# Sheet1.net
KiCad netlist of a schematic drawn in Altium Designer
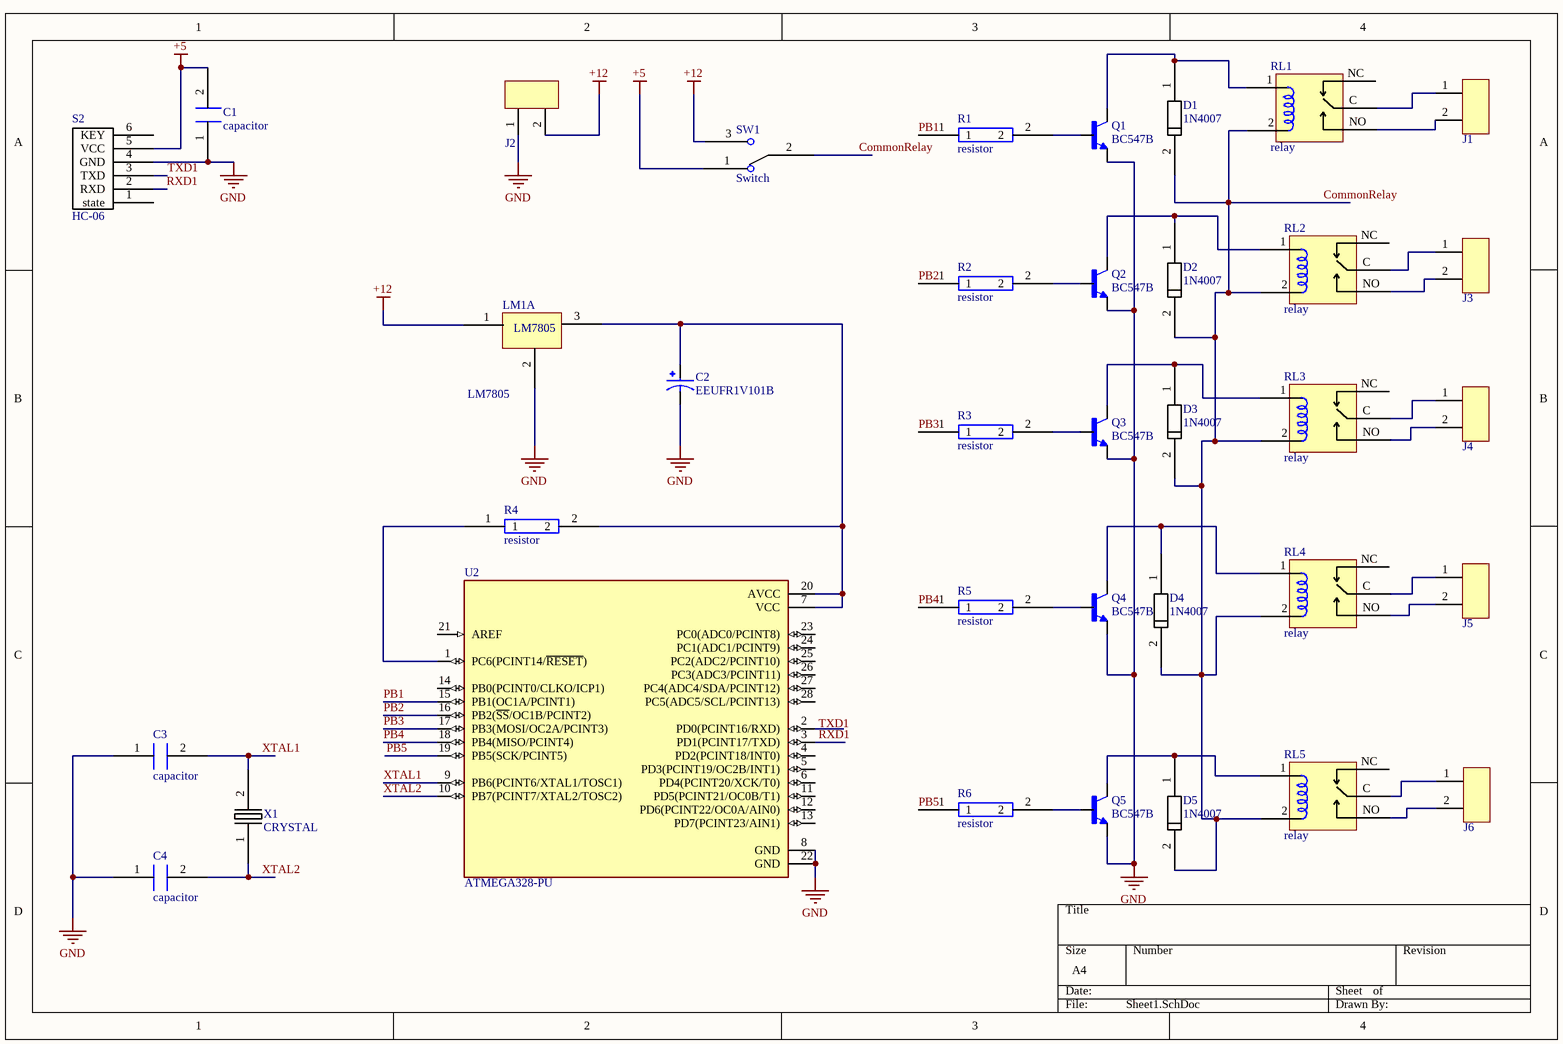
[diagram p0: Sheet1.SchDoc]

(export (version "E")
  (design (tool "Eeschema 10.0.6"))
  (components
    (comp (ref "C1")
      (value "capacitor")
      (footprint "Capacitor")
      (libsource (lib "Schlib1") (part "capacitor"))
    )
    (comp (ref "C2")
      (value "EEUFR1V101B")
      (footprint "CAPPRD350W60D800H1150")
      (description "AL LYTIC, RADIAL, 35VDC, 100UF")
      (fields (field (name "MF") "Panasonic"))
      (libsource (lib "EEUFR1V101B") (part "EEUFR1V101B"))
    )
    (comp (ref "C3")
      (value "capacitor")
      (footprint "Capacitor")
      (libsource (lib "Schlib1") (part "capacitor"))
    )
    (comp (ref "C4")
      (value "capacitor")
      (footprint "Capacitor")
      (libsource (lib "Schlib1") (part "capacitor"))
    )
    (comp (ref "D1") (value "1N4007") (footprint "1N4007") (libsource (lib "Schlib1") (part "1N4007")))
    (comp (ref "D2") (value "1N4007") (footprint "1N4007") (libsource (lib "Schlib1") (part "1N4007")))
    (comp (ref "D3") (value "1N4007") (footprint "1N4007") (libsource (lib "Schlib1") (part "1N4007")))
    (comp (ref "D4") (value "1N4007") (footprint "1N4007") (libsource (lib "Schlib1") (part "1N4007")))
    (comp (ref "D5") (value "1N4007") (footprint "1N4007") (libsource (lib "Schlib1") (part "1N4007")))
    (comp (ref "J1")
      (value "TBP01R1-508-02BE")
      (footprint "TBP01R1-508")
      (description "Conn Shrouded Header HDR 2 POS 5.08mm Solder RA Side Entry Thru-Hole Bag")
      (fields (field (name "MANUFACTURER") "CUI") (field (name "DESIGNED BY") "BERK"))
      (libsource (lib "UDEMY_Library") (part "TBP01R1-508-02BE"))
    )
    (comp (ref "J2")
      (value "TBP01R1-508-02BE")
      (footprint "TBP01R1-508")
      (description "Conn Shrouded Header HDR 2 POS 5.08mm Solder RA Side Entry Thru-Hole Bag")
      (fields (field (name "MANUFACTURER") "CUI") (field (name "DESIGNED BY") "BERK"))
      (libsource (lib "") (part "TBP01R1-508-02BE_1"))
    )
    (comp (ref "J3")
      (value "TBP01R1-508-02BE")
      (footprint "TBP01R1-508")
      (description "Conn Shrouded Header HDR 2 POS 5.08mm Solder RA Side Entry Thru-Hole Bag")
      (fields (field (name "MANUFACTURER") "CUI") (field (name "DESIGNED BY") "BERK"))
      (libsource (lib "UDEMY_Library") (part "TBP01R1-508-02BE"))
    )
    (comp (ref "J4")
      (value "TBP01R1-508-02BE")
      (footprint "TBP01R1-508")
      (description "Conn Shrouded Header HDR 2 POS 5.08mm Solder RA Side Entry Thru-Hole Bag")
      (fields (field (name "MANUFACTURER") "CUI") (field (name "DESIGNED BY") "BERK"))
      (libsource (lib "UDEMY_Library") (part "TBP01R1-508-02BE"))
    )
    (comp (ref "J5")
      (value "TBP01R1-508-02BE")
      (footprint "TBP01R1-508")
      (description "Conn Shrouded Header HDR 2 POS 5.08mm Solder RA Side Entry Thru-Hole Bag")
      (fields (field (name "MANUFACTURER") "CUI") (field (name "DESIGNED BY") "BERK"))
      (libsource (lib "UDEMY_Library") (part "TBP01R1-508-02BE"))
    )
    (comp (ref "J6")
      (value "TBP01R1-508-02BE")
      (footprint "TBP01R1-508")
      (description "Conn Shrouded Header HDR 2 POS 5.08mm Solder RA Side Entry Thru-Hole Bag")
      (fields (field (name "MANUFACTURER") "CUI") (field (name "DESIGNED BY") "BERK"))
      (libsource (lib "UDEMY_Library") (part "TBP01R1-508-02BE"))
    )
    (comp (ref "LM1") (value "LM7805") (footprint "LM7805") (libsource (lib "Schlib1") (part "LM7805")))
    (comp (ref "Q1")
      (value "BC547B")
      (footprint "TO92250P510H770-3")
      (description "Bipolar (BJT) Transistor NPN 45 V 100 mA 300MHz 625 mW Through Hole TO-92 (TO-226)")
      (fields (field (name "MF") "ON Semiconductor"))
      (libsource (lib "BC547B") (part "BC547B"))
    )
    (comp (ref "Q2")
      (value "BC547B")
      (footprint "TO92250P510H770-3")
      (description "Bipolar (BJT) Transistor NPN 45 V 100 mA 300MHz 625 mW Through Hole TO-92 (TO-226)")
      (fields (field (name "MF") "ON Semiconductor"))
      (libsource (lib "BC547B") (part "BC547B"))
    )
    (comp (ref "Q3")
      (value "BC547B")
      (footprint "TO92250P510H770-3")
      (description "Bipolar (BJT) Transistor NPN 45 V 100 mA 300MHz 625 mW Through Hole TO-92 (TO-226)")
      (fields (field (name "MF") "ON Semiconductor"))
      (libsource (lib "BC547B") (part "BC547B"))
    )
    (comp (ref "Q4")
      (value "BC547B")
      (footprint "TO92250P510H770-3")
      (description "Bipolar (BJT) Transistor NPN 45 V 100 mA 300MHz 625 mW Through Hole TO-92 (TO-226)")
      (fields (field (name "MF") "ON Semiconductor"))
      (libsource (lib "BC547B") (part "BC547B"))
    )
    (comp (ref "Q5")
      (value "BC547B")
      (footprint "TO92250P510H770-3")
      (description "Bipolar (BJT) Transistor NPN 45 V 100 mA 300MHz 625 mW Through Hole TO-92 (TO-226)")
      (fields (field (name "MF") "ON Semiconductor"))
      (libsource (lib "BC547B") (part "BC547B"))
    )
    (comp (ref "R1") (value "resistor") (footprint "res") (libsource (lib "Schlib1") (part "resistor")))
    (comp (ref "R2") (value "resistor") (footprint "res") (libsource (lib "Schlib1") (part "resistor")))
    (comp (ref "R3") (value "resistor") (footprint "res") (libsource (lib "Schlib1") (part "resistor")))
    (comp (ref "R4") (value "resistor") (footprint "res") (libsource (lib "Schlib1") (part "resistor")))
    (comp (ref "R5") (value "resistor") (footprint "res") (libsource (lib "Schlib1") (part "resistor")))
    (comp (ref "R6") (value "resistor") (footprint "res") (libsource (lib "Schlib1") (part "resistor")))
    (comp (ref "RL1") (value "relay") (footprint "relay") (libsource (lib "Schlib1") (part "relay")))
    (comp (ref "RL2") (value "relay") (footprint "relay") (libsource (lib "Schlib1") (part "relay")))
    (comp (ref "RL3") (value "relay") (footprint "relay") (libsource (lib "Schlib1") (part "relay")))
    (comp (ref "RL4") (value "relay") (footprint "relay") (libsource (lib "Schlib1") (part "relay")))
    (comp (ref "RL5") (value "relay") (footprint "relay") (libsource (lib "Schlib1") (part "relay")))
    (comp (ref "S2") (value "HC-06") (footprint "HC-06") (libsource (lib "Schlib1") (part "HC-06")))
    (comp (ref "SW1")
      (value "Switch")
      (footprint "toggle switch")
      (libsource (lib "Schlib1") (part "Switch"))
    )
    (comp (ref "U2")
      (value "ATMEGA328-PU")
      (footprint "DIP787W46P254L3467H508Q28")
      (description "AVR AVRÂ® ATmega Microcontroller IC 8-Bit 20MHz 32KB (16K x 16) FLASH 28-PDIP")
      (fields (field (name "MF") "Microchip Technology"))
      (libsource (lib "ATMEGA328-PU") (part "ATMEGA328-PU"))
    )
    (comp (ref "X1") (value "CRYSTAL") (footprint "CRYSTAL") (libsource (lib "Schlib1") (part "CRYSTAL")))
  )
  (nets
    (net (code "1") (name "+5") (class "Default")
      (node (ref "C1") (pin "2") (pintype "passive"))
      (node (ref "S2") (pin "5") (pinfunction "VCC_5") (pintype "passive"))
      (node (ref "SW1") (pin "1") (pinfunction "1_1") (pintype "passive"))
    )
    (net (code "2") (name "+12") (class "Default")
      (node (ref "J2") (pin "2") (pinfunction "2_2") (pintype "power_in"))
      (node (ref "LM1") (pin "1") (pinfunction "in_1") (pintype "passive"))
      (node (ref "SW1") (pin "3") (pinfunction "3_3") (pintype "passive"))
    )
    (net (code "3") (name "/CommonRelay") (class "Default")
      (node (ref "D1") (pin "2") (pinfunction "katot_2") (pintype "passive"))
      (node (ref "D2") (pin "2") (pinfunction "katot_2") (pintype "passive"))
      (node (ref "D3") (pin "2") (pinfunction "katot_2") (pintype "passive"))
      (node (ref "D4") (pin "2") (pinfunction "katot_2") (pintype "passive"))
      (node (ref "D5") (pin "2") (pinfunction "katot_2") (pintype "passive"))
      (node (ref "RL1") (pin "2") (pinfunction "2_2") (pintype "passive"))
      (node (ref "RL2") (pin "2") (pinfunction "2_2") (pintype "passive"))
      (node (ref "RL3") (pin "2") (pinfunction "2_2") (pintype "passive"))
      (node (ref "RL4") (pin "2") (pinfunction "2_2") (pintype "passive"))
      (node (ref "RL5") (pin "2") (pinfunction "2_2") (pintype "passive"))
      (node (ref "SW1") (pin "2") (pinfunction "2_2") (pintype "passive"))
    )
    (net (code "4") (name "/PB1") (class "Default")
      (node (ref "R1") (pin "1") (pinfunction "1_1") (pintype "passive"))
      (node (ref "U2") (pin "15") (pinfunction "PB1(OC1A/PCINT1)_15") (pintype "bidirectional"))
    )
    (net (code "5") (name "/PB2") (class "Default")
      (node (ref "R2") (pin "1") (pinfunction "1_1") (pintype "passive"))
      (node (ref "U2") (pin "16") (pinfunction "PB2(~{SS}/OC1B/PCINT2)_16") (pintype "bidirectional"))
    )
    (net (code "6") (name "/PB3") (class "Default")
      (node (ref "R3") (pin "1") (pinfunction "1_1") (pintype "passive"))
      (node (ref "U2") (pin "17") (pinfunction "PB3(MOSI/OC2A/PCINT3)_17") (pintype "bidirectional"))
    )
    (net (code "7") (name "/PB4") (class "Default")
      (node (ref "R5") (pin "1") (pinfunction "1_1") (pintype "passive"))
      (node (ref "U2") (pin "18") (pinfunction "PB4(MISO/PCINT4)_18") (pintype "bidirectional"))
    )
    (net (code "8") (name "/PB5") (class "Default")
      (node (ref "R6") (pin "1") (pinfunction "1_1") (pintype "passive"))
      (node (ref "U2") (pin "19") (pinfunction "PB5(SCK/PCINT5)_19") (pintype "bidirectional"))
    )
    (net (code "9") (name "/RXD1") (class "Default")
      (node (ref "S2") (pin "2") (pinfunction "RXD_2") (pintype "passive"))
      (node (ref "U2") (pin "3") (pinfunction "PD1(PCINT17/TXD)_3") (pintype "bidirectional"))
    )
    (net (code "10") (name "/TXD1") (class "Default")
      (node (ref "S2") (pin "3") (pinfunction "TXD_3") (pintype "passive"))
    )
    (net (code "11") (name "/XTAL1") (class "Default")
      (node (ref "C3") (pin "2") (pintype "passive"))
      (node (ref "U2") (pin "9") (pinfunction "PB6(PCINT6/XTAL1/TOSC1)_9") (pintype "bidirectional"))
      (node (ref "X1") (pin "2") (pinfunction "2_2") (pintype "passive"))
    )
    (net (code "12") (name "/XTAL2") (class "Default")
      (node (ref "C4") (pin "2") (pintype "passive"))
      (node (ref "U2") (pin "10") (pinfunction "PB7(PCINT7/XTAL2/TOSC2)_10") (pintype "bidirectional"))
      (node (ref "X1") (pin "1") (pinfunction "4_1") (pintype "passive"))
    )
    (net (code "13") (name "GND") (class "Default")
      (node (ref "C1") (pin "1") (pintype "passive"))
      (node (ref "C2") (pin "N") (pinfunction "N_N") (pintype "passive"))
      (node (ref "C3") (pin "1") (pintype "passive"))
      (node (ref "C4") (pin "1") (pintype "passive"))
      (node (ref "J2") (pin "1") (pinfunction "1_1") (pintype "power_in"))
      (node (ref "LM1") (pin "2") (pinfunction "GND_2") (pintype "passive"))
      (node (ref "Q1") (pin "3") (pinfunction "E_3") (pintype "passive"))
      (node (ref "Q2") (pin "3") (pinfunction "E_3") (pintype "passive"))
      (node (ref "Q3") (pin "3") (pinfunction "E_3") (pintype "passive"))
      (node (ref "Q4") (pin "3") (pinfunction "E_3") (pintype "passive"))
      (node (ref "Q5") (pin "3") (pinfunction "E_3") (pintype "passive"))
      (node (ref "S2") (pin "4") (pinfunction "GND_4") (pintype "passive"))
      (node (ref "U2") (pin "22") (pinfunction "GND_22") (pintype "power_in"))
      (node (ref "U2") (pin "8") (pinfunction "GND_8") (pintype "power_in"))
    )
    (net (code "14") (name "Net-(D1-anot)") (class "Default")
      (node (ref "D1") (pin "1") (pinfunction "anot_1") (pintype "passive"))
      (node (ref "Q1") (pin "1") (pinfunction "C_1") (pintype "passive"))
      (node (ref "RL1") (pin "1") (pinfunction "1_1") (pintype "passive"))
    )
    (net (code "15") (name "Net-(D2-anot)") (class "Default")
      (node (ref "D2") (pin "1") (pinfunction "anot_1") (pintype "passive"))
      (node (ref "Q2") (pin "1") (pinfunction "C_1") (pintype "passive"))
      (node (ref "RL2") (pin "1") (pinfunction "1_1") (pintype "passive"))
    )
    (net (code "16") (name "Net-(D3-anot)") (class "Default")
      (node (ref "D3") (pin "1") (pinfunction "anot_1") (pintype "passive"))
      (node (ref "Q3") (pin "1") (pinfunction "C_1") (pintype "passive"))
      (node (ref "RL3") (pin "1") (pinfunction "1_1") (pintype "passive"))
    )
    (net (code "17") (name "Net-(D4-anot)") (class "Default")
      (node (ref "D4") (pin "1") (pinfunction "anot_1") (pintype "passive"))
      (node (ref "Q4") (pin "1") (pinfunction "C_1") (pintype "passive"))
      (node (ref "RL4") (pin "1") (pinfunction "1_1") (pintype "passive"))
    )
    (net (code "18") (name "Net-(D5-anot)") (class "Default")
      (node (ref "D5") (pin "1") (pinfunction "anot_1") (pintype "passive"))
      (node (ref "Q5") (pin "1") (pinfunction "C_1") (pintype "passive"))
      (node (ref "RL5") (pin "1") (pinfunction "1_1") (pintype "passive"))
    )
    (net (code "19") (name "Net-(J1-Pad1)") (class "Default")
      (node (ref "J1") (pin "1") (pinfunction "1_1") (pintype "power_in"))
      (node (ref "RL1") (pin "C") (pinfunction "C_C") (pintype "passive"))
    )
    (net (code "20") (name "Net-(J1-Pad2)") (class "Default")
      (node (ref "J1") (pin "2") (pinfunction "2_2") (pintype "power_in"))
      (node (ref "RL1") (pin "NO") (pinfunction "NO_NO") (pintype "passive"))
    )
    (net (code "21") (name "Net-(J3-Pad1)") (class "Default")
      (node (ref "J3") (pin "1") (pinfunction "1_1") (pintype "power_in"))
      (node (ref "RL2") (pin "C") (pinfunction "C_C") (pintype "passive"))
    )
    (net (code "22") (name "Net-(J3-Pad2)") (class "Default")
      (node (ref "J3") (pin "2") (pinfunction "2_2") (pintype "power_in"))
      (node (ref "RL2") (pin "NO") (pinfunction "NO_NO") (pintype "passive"))
    )
    (net (code "23") (name "Net-(J4-Pad1)") (class "Default")
      (node (ref "J4") (pin "1") (pinfunction "1_1") (pintype "power_in"))
      (node (ref "RL3") (pin "C") (pinfunction "C_C") (pintype "passive"))
    )
    (net (code "24") (name "Net-(J4-Pad2)") (class "Default")
      (node (ref "J4") (pin "2") (pinfunction "2_2") (pintype "power_in"))
      (node (ref "RL3") (pin "NO") (pinfunction "NO_NO") (pintype "passive"))
    )
    (net (code "25") (name "Net-(J5-Pad1)") (class "Default")
      (node (ref "J5") (pin "1") (pinfunction "1_1") (pintype "power_in"))
      (node (ref "RL4") (pin "C") (pinfunction "C_C") (pintype "passive"))
    )
    (net (code "26") (name "Net-(J5-Pad2)") (class "Default")
      (node (ref "J5") (pin "2") (pinfunction "2_2") (pintype "power_in"))
      (node (ref "RL4") (pin "NO") (pinfunction "NO_NO") (pintype "passive"))
    )
    (net (code "27") (name "Net-(J6-Pad1)") (class "Default")
      (node (ref "J6") (pin "1") (pinfunction "1_1") (pintype "power_in"))
      (node (ref "RL5") (pin "C") (pinfunction "C_C") (pintype "passive"))
    )
    (net (code "28") (name "Net-(J6-Pad2)") (class "Default")
      (node (ref "J6") (pin "2") (pinfunction "2_2") (pintype "power_in"))
      (node (ref "RL5") (pin "NO") (pinfunction "NO_NO") (pintype "passive"))
    )
    (net (code "29") (name "Net-(LM1A-out)") (class "Default")
      (node (ref "C2") (pin "P") (pinfunction "P_P") (pintype "passive"))
      (node (ref "LM1") (pin "3") (pinfunction "out_3") (pintype "passive"))
      (node (ref "R4") (pin "2") (pinfunction "2_2") (pintype "passive"))
      (node (ref "U2") (pin "20") (pinfunction "AVCC_20") (pintype "power_in"))
      (node (ref "U2") (pin "7") (pinfunction "VCC_7") (pintype "power_in"))
    )
    (net (code "30") (name "Net-(Q1-B)") (class "Default")
      (node (ref "Q1") (pin "2") (pinfunction "B_2") (pintype "passive"))
      (node (ref "R1") (pin "2") (pinfunction "2_2") (pintype "passive"))
    )
    (net (code "31") (name "Net-(Q2-B)") (class "Default")
      (node (ref "Q2") (pin "2") (pinfunction "B_2") (pintype "passive"))
      (node (ref "R2") (pin "2") (pinfunction "2_2") (pintype "passive"))
    )
    (net (code "32") (name "Net-(Q3-B)") (class "Default")
      (node (ref "Q3") (pin "2") (pinfunction "B_2") (pintype "passive"))
      (node (ref "R3") (pin "2") (pinfunction "2_2") (pintype "passive"))
    )
    (net (code "33") (name "Net-(Q4-B)") (class "Default")
      (node (ref "Q4") (pin "2") (pinfunction "B_2") (pintype "passive"))
      (node (ref "R5") (pin "2") (pinfunction "2_2") (pintype "passive"))
    )
    (net (code "34") (name "Net-(Q5-B)") (class "Default")
      (node (ref "Q5") (pin "2") (pinfunction "B_2") (pintype "passive"))
      (node (ref "R6") (pin "2") (pinfunction "2_2") (pintype "passive"))
    )
    (net (code "35") (name "Net-(U2-PC6(PCINT14{slash}~{RESET}))") (class "Default")
      (node (ref "R4") (pin "1") (pinfunction "1_1") (pintype "passive"))
      (node (ref "U2") (pin "1") (pinfunction "PC6(PCINT14/~{RESET})_1") (pintype "bidirectional"))
    )
    (net (code "36") (name "unconnected-(RL1-PadNC)") (class "Default")
      (node (ref "RL1") (pin "NC") (pinfunction "NC_NC") (pintype "passive"))
    )
    (net (code "37") (name "unconnected-(RL2-PadNC)") (class "Default")
      (node (ref "RL2") (pin "NC") (pinfunction "NC_NC") (pintype "passive"))
    )
    (net (code "38") (name "unconnected-(RL3-PadNC)") (class "Default")
      (node (ref "RL3") (pin "NC") (pinfunction "NC_NC") (pintype "passive"))
    )
    (net (code "39") (name "unconnected-(RL4-PadNC)") (class "Default")
      (node (ref "RL4") (pin "NC") (pinfunction "NC_NC") (pintype "passive"))
    )
    (net (code "40") (name "unconnected-(RL5-PadNC)") (class "Default")
      (node (ref "RL5") (pin "NC") (pinfunction "NC_NC") (pintype "passive"))
    )
    (net (code "41") (name "unconnected-(S2-KEY-Pad6)") (class "Default")
      (node (ref "S2") (pin "6") (pinfunction "KEY_6") (pintype "passive"))
    )
    (net (code "42") (name "unconnected-(S2-state-Pad1)") (class "Default")
      (node (ref "S2") (pin "1") (pinfunction "state_1") (pintype "passive"))
    )
    (net (code "43") (name "unconnected-(U2-AREF-Pad21)") (class "Default")
      (node (ref "U2") (pin "21") (pinfunction "AREF_21") (pintype "input"))
    )
    (net (code "44") (name "unconnected-(U2-PB0(PCINT0{slash}CLKO{slash}ICP1)-Pad14)") (class "Default")
      (node (ref "U2") (pin "14") (pinfunction "PB0(PCINT0/CLKO/ICP1)_14") (pintype "bidirectional"))
    )
    (net (code "45") (name "unconnected-(U2-PC0(ADC0{slash}PCINT8)-Pad23)") (class "Default")
      (node (ref "U2") (pin "23") (pinfunction "PC0(ADC0/PCINT8)_23") (pintype "bidirectional"))
    )
    (net (code "46") (name "unconnected-(U2-PC1(ADC1{slash}PCINT9)-Pad24)") (class "Default")
      (node (ref "U2") (pin "24") (pinfunction "PC1(ADC1/PCINT9)_24") (pintype "bidirectional"))
    )
    (net (code "47") (name "unconnected-(U2-PC2(ADC2{slash}PCINT10)-Pad25)") (class "Default")
      (node (ref "U2") (pin "25") (pinfunction "PC2(ADC2/PCINT10)_25") (pintype "bidirectional"))
    )
    (net (code "48") (name "unconnected-(U2-PC3(ADC3{slash}PCINT11)-Pad26)") (class "Default")
      (node (ref "U2") (pin "26") (pinfunction "PC3(ADC3/PCINT11)_26") (pintype "bidirectional"))
    )
    (net (code "49") (name "unconnected-(U2-PC4(ADC4{slash}SDA{slash}PCINT12)-Pad27)") (class "Default")
      (node (ref "U2") (pin "27") (pinfunction "PC4(ADC4/SDA/PCINT12)_27") (pintype "bidirectional"))
    )
    (net (code "50") (name "unconnected-(U2-PC5(ADC5{slash}SCL{slash}PCINT13)-Pad28)") (class "Default")
      (node (ref "U2") (pin "28") (pinfunction "PC5(ADC5/SCL/PCINT13)_28") (pintype "bidirectional"))
    )
    (net (code "51") (name "unconnected-(U2-PD0(PCINT16{slash}RXD)-Pad2)") (class "Default")
      (node (ref "U2") (pin "2") (pinfunction "PD0(PCINT16/RXD)_2") (pintype "bidirectional"))
    )
    (net (code "52") (name "unconnected-(U2-PD2(PCINT18{slash}INT0)-Pad4)") (class "Default")
      (node (ref "U2") (pin "4") (pinfunction "PD2(PCINT18/INT0)_4") (pintype "bidirectional"))
    )
    (net (code "53") (name "unconnected-(U2-PD3(PCINT19{slash}OC2B{slash}INT1)-Pad5)") (class "Default")
      (node (ref "U2") (pin "5") (pinfunction "PD3(PCINT19/OC2B/INT1)_5") (pintype "bidirectional"))
    )
    (net (code "54") (name "unconnected-(U2-PD4(PCINT20{slash}XCK{slash}T0)-Pad6)") (class "Default")
      (node (ref "U2") (pin "6") (pinfunction "PD4(PCINT20/XCK/T0)_6") (pintype "bidirectional"))
    )
    (net (code "55") (name "unconnected-(U2-PD5(PCINT21{slash}OC0B{slash}T1)-Pad11)") (class "Default")
      (node (ref "U2") (pin "11") (pinfunction "PD5(PCINT21/OC0B/T1)_11") (pintype "bidirectional"))
    )
    (net (code "56") (name "unconnected-(U2-PD6(PCINT22{slash}OC0A{slash}AIN0)-Pad12)") (class "Default")
      (node (ref "U2") (pin "12") (pinfunction "PD6(PCINT22/OC0A/AIN0)_12") (pintype "bidirectional"))
    )
    (net (code "57") (name "unconnected-(U2-PD7(PCINT23{slash}AIN1)-Pad13)") (class "Default")
      (node (ref "U2") (pin "13") (pinfunction "PD7(PCINT23/AIN1)_13") (pintype "bidirectional"))
    )
  )
)
